# MRCS-Remote-Switch-Motor-Controller-Rela.net
KiCad netlist of a schematic drawn in EAGLE
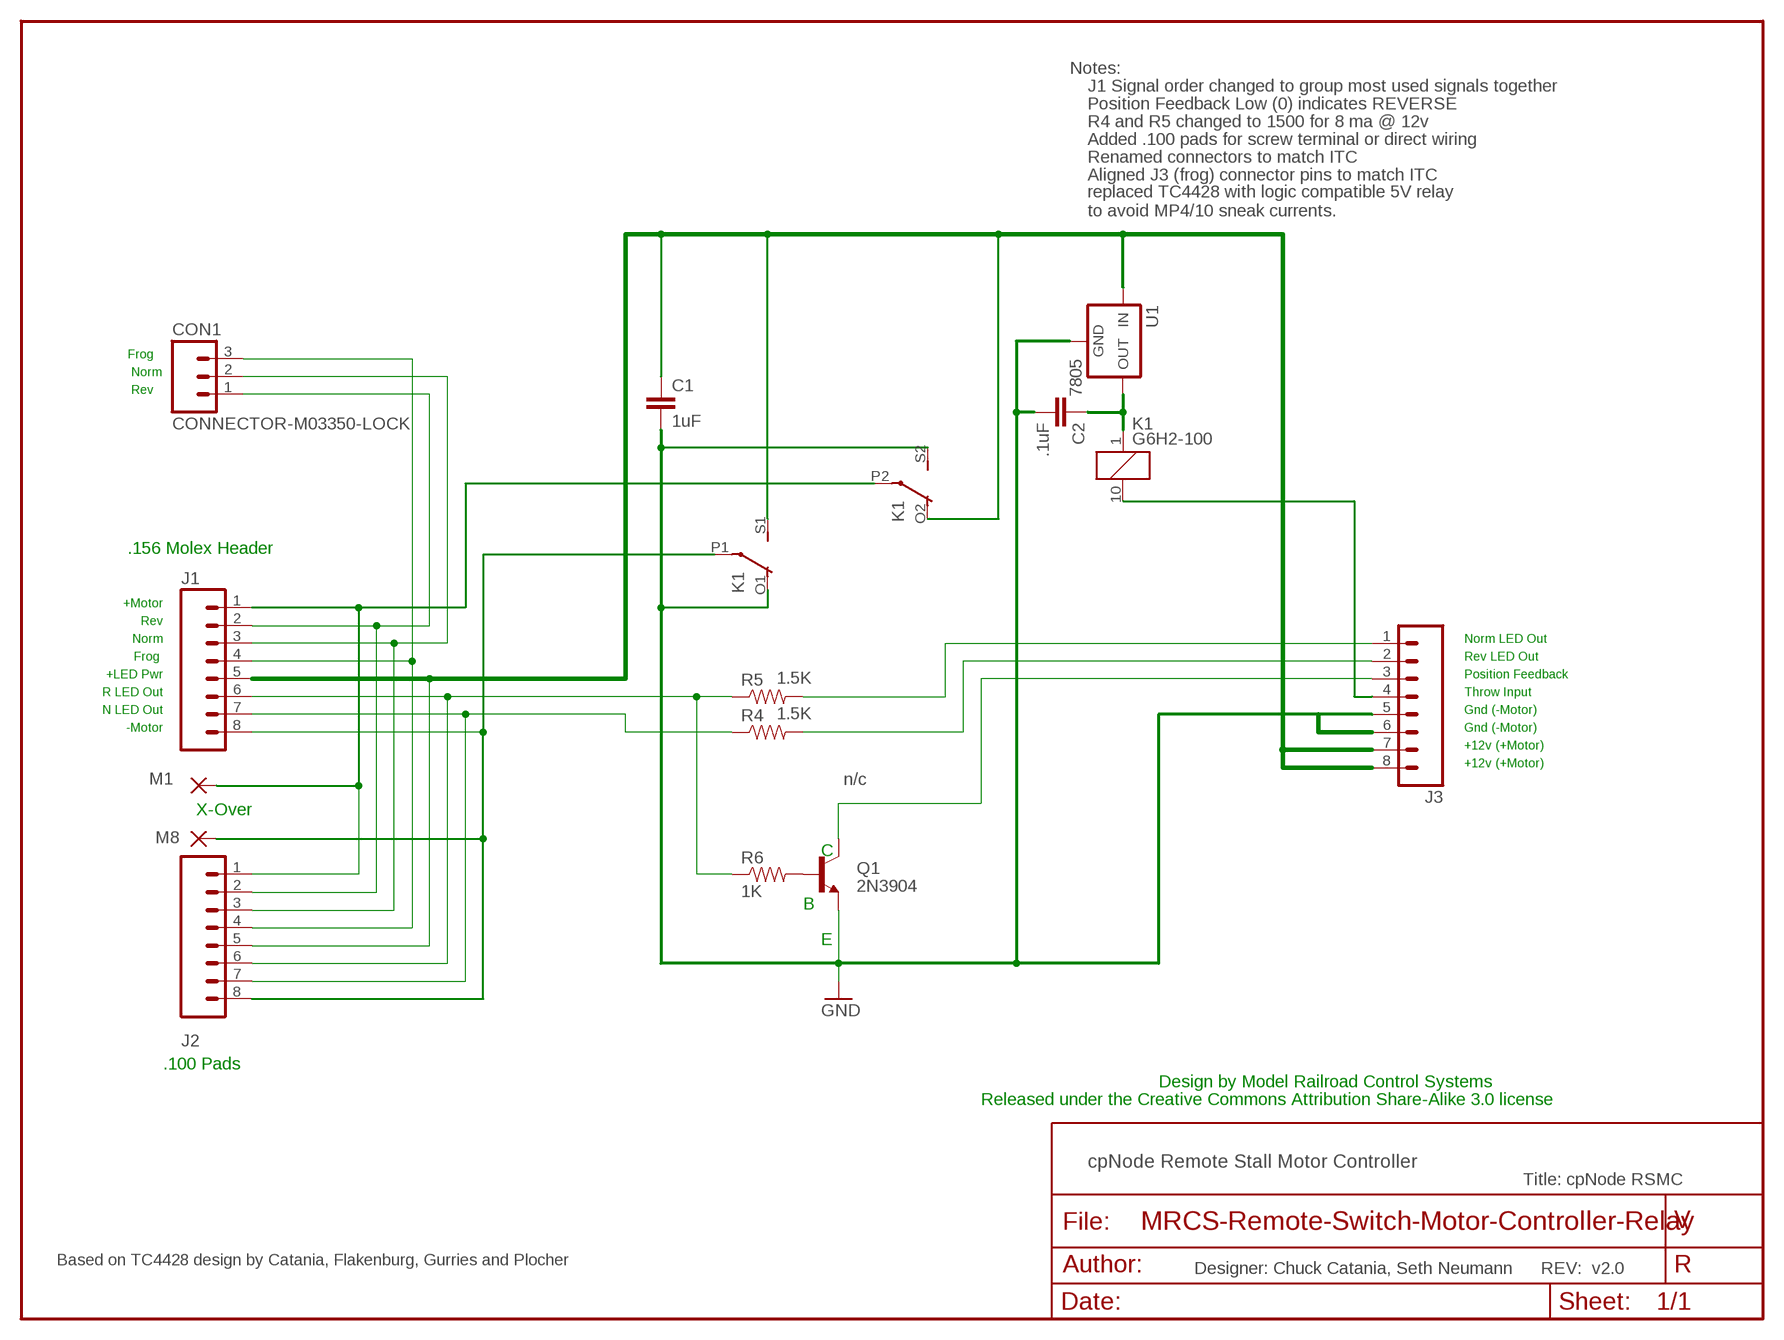
[diagram p0: schematic, sheet 1]

(export (version "E")
  (design (tool "Eeschema 10.0.6"))
  (components
    (comp (ref "C1")
      (value "1uF")
      (footprint "eagle-import:CAP-PTH-SMALLEZ")
      (libsource (lib "eagle-import") (part "CAPEZ"))
    )
    (comp (ref "C2")
      (value ".1uF")
      (footprint "eagle-import:CAP-PTH-SMALLEZ")
      (libsource (lib "eagle-import") (part "CAPEZ"))
    )
    (comp (ref "CON1")
      (value "CONNECTOR-M03350-LOCK")
      (footprint "eagle-import:1751251")
      (libsource (lib "eagle-import") (part "CONNECTOR-M03350-LOCK"))
    )
    (comp (ref "J1")
      (value "J1")
      (footprint "eagle-import:KK-156-8-F")
      (libsource (lib "eagle-import") (part "CONNECTOR-M081.56-F"))
    )
    (comp (ref "J2")
      (value "J2")
      (footprint "eagle-import:1X08_PIN1_NO_SILK")
      (libsource (lib "eagle-import") (part "M08"))
    )
    (comp (ref "J3")
      (value "CONNECTOR-M08LOCK")
      (footprint "eagle-import:1X08_LOCK")
      (libsource (lib "eagle-import") (part "CONNECTOR-M08LOCK"))
    )
    (comp (ref "K1")
      (value "G6H2-100")
      (footprint "eagle-import:G6H2-100")
      (libsource (lib "eagle-import") (part "G6H2-100"))
    )
    (comp (ref "M1")
      (value "WIREPAD2,54/1,1")
      (footprint "eagle-import:2,54_1,1")
      (libsource (lib "eagle-import") (part "WIREPAD2,54/1,1"))
    )
    (comp (ref "M8")
      (value "WIREPAD2,54/1,1")
      (footprint "eagle-import:2,54_1,1")
      (libsource (lib "eagle-import") (part "WIREPAD2,54/1,1"))
    )
    (comp (ref "Q1")
      (value "2N3904")
      (footprint "eagle-import:TO-92-MS013")
      (libsource (lib "eagle-import") (part "NPN-MS-013"))
    )
    (comp (ref "R4")
      (value "1.5K")
      (footprint "eagle-import:AXIAL-0.4-RES")
      (libsource (lib "eagle-import") (part "RPTH04"))
    )
    (comp (ref "R5")
      (value "1.5K")
      (footprint "eagle-import:AXIAL-0.4-RES")
      (libsource (lib "eagle-import") (part "RPTH04"))
    )
    (comp (ref "R6")
      (value "1K")
      (footprint "eagle-import:AXIAL-0.4-RES")
      (libsource (lib "eagle-import") (part "RPTH04"))
    )
    (comp (ref "U1")
      (value "7805")
      (footprint "eagle-import:TO92D-")
      (libsource (lib "eagle-import") (part "78XX-TO92"))
    )
  )
  (nets
    (net (code "1") (name "GND") (class "Default")
      (node (ref "C1") (pin "2") (pinfunction "2_2") (pintype "passive"))
      (node (ref "C2") (pin "2") (pinfunction "2_2") (pintype "passive"))
      (node (ref "J3") (pin "5") (pinfunction "5_5") (pintype "passive"))
      (node (ref "J3") (pin "6") (pinfunction "6_6") (pintype "passive"))
      (node (ref "K1") (pin "O1") (pinfunction "O_O1") (pintype "passive"))
      (node (ref "K1") (pin "S2") (pinfunction "S_S2") (pintype "passive"))
      (node (ref "Q1") (pin "1") (pinfunction "E_1") (pintype "passive"))
      (node (ref "U1") (pin "2") (pinfunction "GND_2") (pintype "power_in"))
    )
    (net (code "2") (name "Net-(CON1-Pad1)") (class "Default")
      (node (ref "CON1") (pin "1") (pinfunction "1_1") (pintype "passive"))
      (node (ref "J1") (pin "2") (pinfunction "2_2") (pintype "passive"))
      (node (ref "J2") (pin "2") (pinfunction "2_2") (pintype "passive"))
    )
    (net (code "3") (name "Net-(CON1-Pad2)") (class "Default")
      (node (ref "CON1") (pin "2") (pinfunction "2_2") (pintype "passive"))
      (node (ref "J1") (pin "3") (pinfunction "3_3") (pintype "passive"))
      (node (ref "J2") (pin "3") (pinfunction "3_3") (pintype "passive"))
    )
    (net (code "4") (name "Net-(CON1-Pad3)") (class "Default")
      (node (ref "CON1") (pin "3") (pinfunction "3_3") (pintype "passive"))
      (node (ref "J1") (pin "4") (pinfunction "4_4") (pintype "passive"))
      (node (ref "J2") (pin "4") (pinfunction "4_4") (pintype "passive"))
    )
    (net (code "5") (name "Net-(K1A-2)") (class "Default")
      (node (ref "J3") (pin "4") (pinfunction "4_4") (pintype "passive"))
      (node (ref "K1") (pin "10") (pinfunction "2_10") (pintype "passive"))
    )
    (net (code "6") (name "Net-(K1B-P)") (class "Default")
      (node (ref "J1") (pin "8") (pinfunction "8_8") (pintype "passive"))
      (node (ref "J2") (pin "8") (pinfunction "8_8") (pintype "passive"))
      (node (ref "K1") (pin "P1") (pinfunction "P_P1") (pintype "passive"))
      (node (ref "M8") (pin "1") (pinfunction "P_1") (pintype "passive"))
    )
    (net (code "7") (name "Net-(K1B-S)") (class "Default")
      (node (ref "C1") (pin "1") (pinfunction "1_1") (pintype "passive"))
      (node (ref "J1") (pin "5") (pinfunction "5_5") (pintype "passive"))
      (node (ref "J2") (pin "5") (pinfunction "5_5") (pintype "passive"))
      (node (ref "J3") (pin "7") (pinfunction "7_7") (pintype "passive"))
      (node (ref "J3") (pin "8") (pinfunction "8_8") (pintype "passive"))
      (node (ref "K1") (pin "O2") (pinfunction "O_O2") (pintype "passive"))
      (node (ref "K1") (pin "S1") (pinfunction "S_S1") (pintype "passive"))
      (node (ref "U1") (pin "1") (pinfunction "VIN_1") (pintype "power_in"))
    )
    (net (code "8") (name "Net-(K1C-P)") (class "Default")
      (node (ref "J1") (pin "1") (pinfunction "1_1") (pintype "passive"))
      (node (ref "J2") (pin "1") (pinfunction "1_1") (pintype "passive"))
      (node (ref "K1") (pin "P2") (pinfunction "P_P2") (pintype "passive"))
      (node (ref "M1") (pin "1") (pinfunction "P_1") (pintype "passive"))
    )
    (net (code "9") (name "Net-(Q1-B)") (class "Default")
      (node (ref "Q1") (pin "2") (pinfunction "B_2") (pintype "passive"))
      (node (ref "R6") (pin "P$2") (pinfunction "2_P$2") (pintype "passive"))
    )
    (net (code "10") (name "Net-(Q1-C)") (class "Default")
      (node (ref "J3") (pin "3") (pinfunction "3_3") (pintype "passive"))
      (node (ref "Q1") (pin "3") (pinfunction "C_3") (pintype "passive"))
    )
    (net (code "11") (name "Net-(R4-1)") (class "Default")
      (node (ref "J1") (pin "7") (pinfunction "7_7") (pintype "passive"))
      (node (ref "J2") (pin "7") (pinfunction "7_7") (pintype "passive"))
      (node (ref "R4") (pin "P$1") (pinfunction "1_P$1") (pintype "passive"))
    )
    (net (code "12") (name "Net-(R4-2)") (class "Default")
      (node (ref "J3") (pin "2") (pinfunction "2_2") (pintype "passive"))
      (node (ref "R4") (pin "P$2") (pinfunction "2_P$2") (pintype "passive"))
    )
    (net (code "13") (name "Net-(R5-1)") (class "Default")
      (node (ref "J1") (pin "6") (pinfunction "6_6") (pintype "passive"))
      (node (ref "J2") (pin "6") (pinfunction "6_6") (pintype "passive"))
      (node (ref "R5") (pin "P$1") (pinfunction "1_P$1") (pintype "passive"))
      (node (ref "R6") (pin "P$1") (pinfunction "1_P$1") (pintype "passive"))
    )
    (net (code "14") (name "Net-(R5-2)") (class "Default")
      (node (ref "J3") (pin "1") (pinfunction "1_1") (pintype "passive"))
      (node (ref "R5") (pin "P$2") (pinfunction "2_P$2") (pintype "passive"))
    )
    (net (code "15") (name "Net-(U1-VOUT)") (class "Default")
      (node (ref "C2") (pin "1") (pinfunction "1_1") (pintype "passive"))
      (node (ref "K1") (pin "1") (pinfunction "1_1") (pintype "passive"))
      (node (ref "U1") (pin "3") (pinfunction "VOUT_3") (pintype "power_in"))
    )
  )
)
